# ESP32_WROVER_iot_module.net
KiCad netlist of a schematic drawn in EAGLE
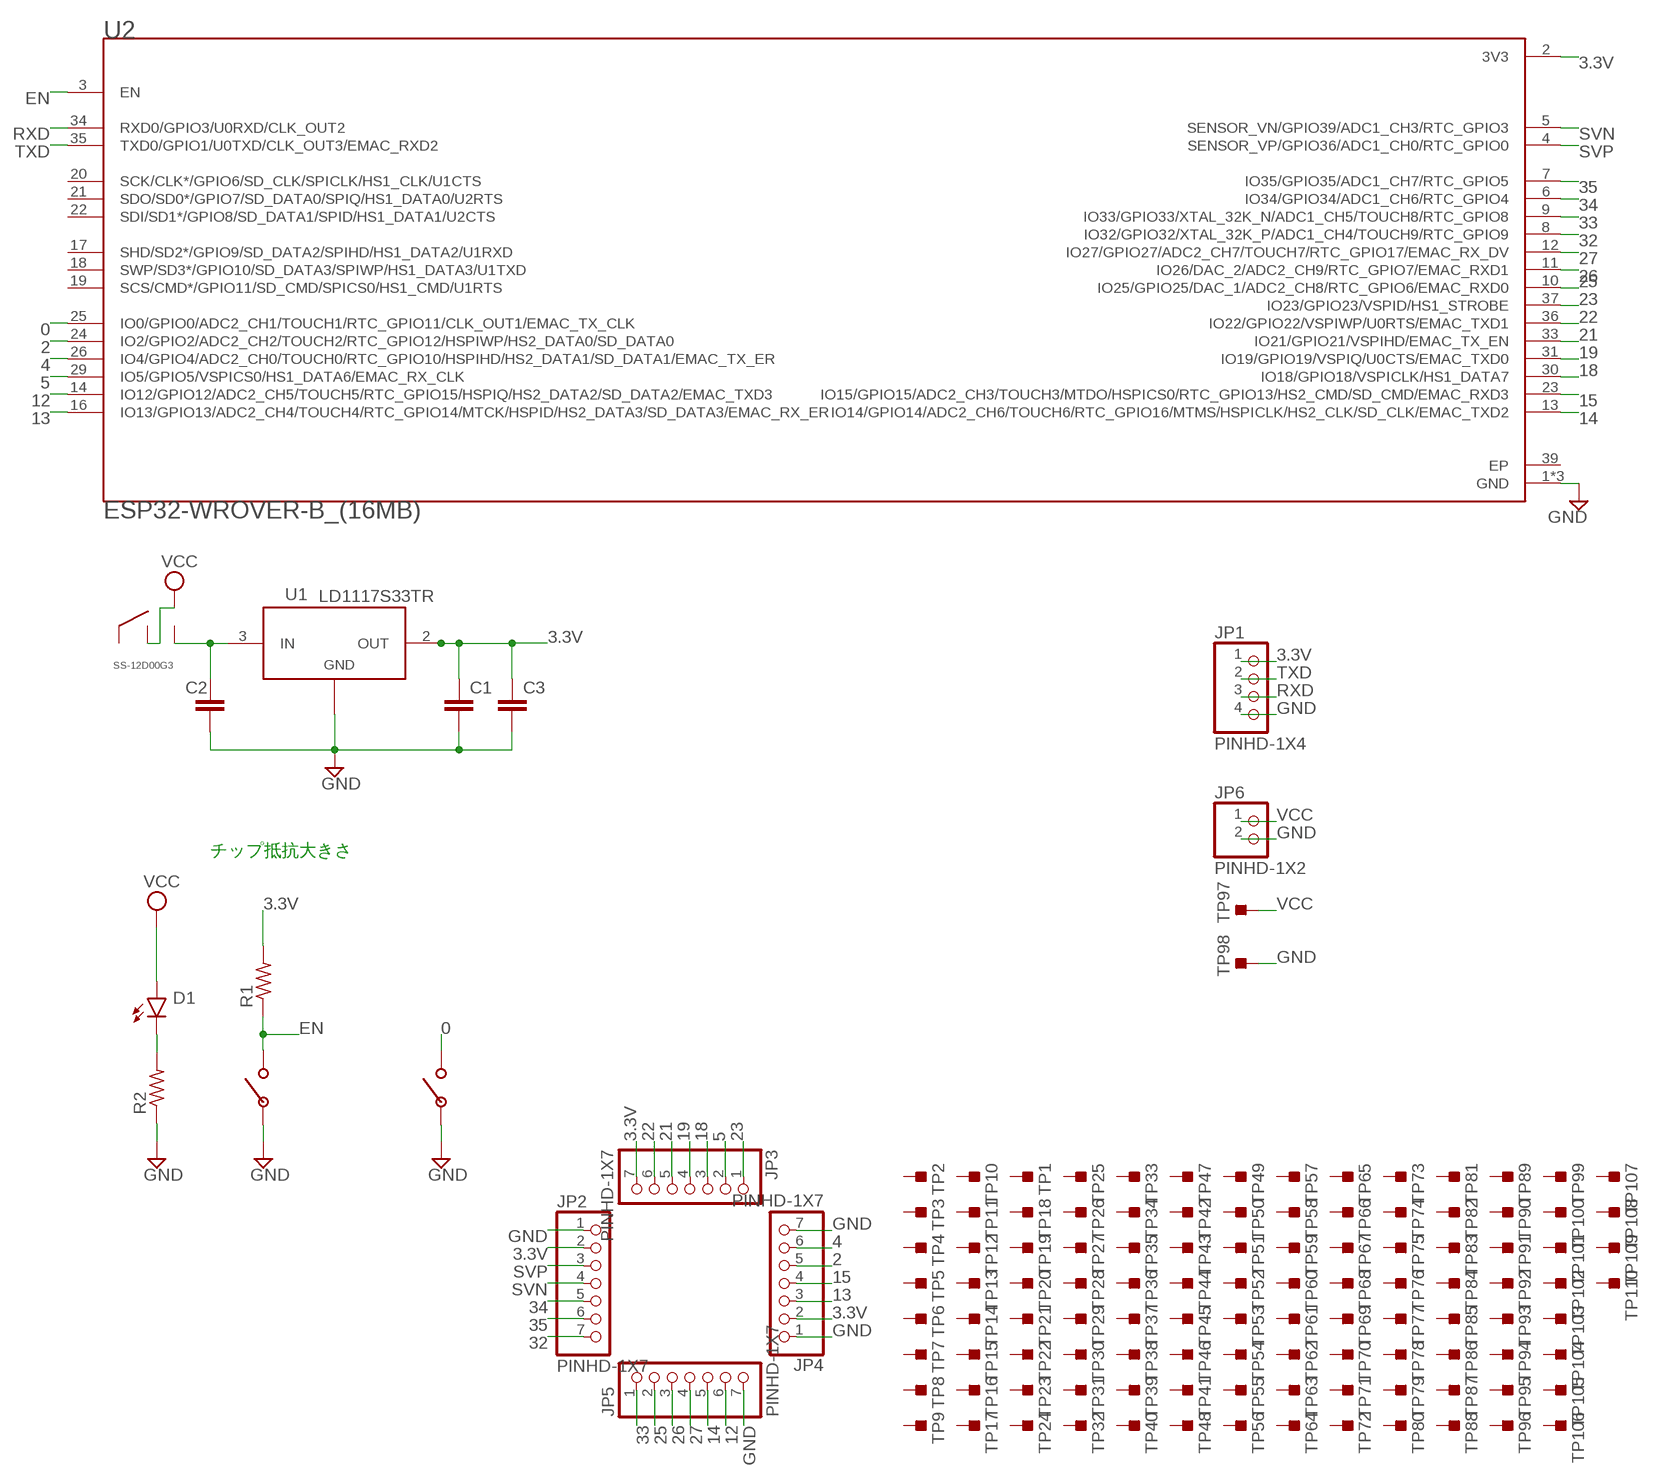
[diagram p0: schematic, sheet 1]

(export (version "E")
  (design (tool "Eeschema 10.0.6"))
  (components
    (comp (ref "C1")
      (value "C-EUC0805K")
      (footprint "eagle-import:C0805K")
      (libsource (lib "eagle-import") (part "C-EUC0805K"))
    )
    (comp (ref "C2")
      (value "C-EUC0805K")
      (footprint "eagle-import:C0805K")
      (libsource (lib "eagle-import") (part "C-EUC0805K"))
    )
    (comp (ref "C3")
      (value "C-EUC0805K")
      (footprint "eagle-import:C0805K")
      (libsource (lib "eagle-import") (part "C-EUC0805K"))
    )
    (comp (ref "D1")
      (value "LED_BLUE")
      (footprint "eagle-import:LEDC1608X39N_B")
      (libsource (lib "eagle-import") (part "LED_CHIPBLUE-1608_"))
    )
    (comp (ref "JP1")
      (value "PINHD-1X4")
      (footprint "eagle-import:1X04")
      (libsource (lib "eagle-import") (part "PINHD-1X4"))
    )
    (comp (ref "JP2")
      (value "PINHD-1X7")
      (footprint "eagle-import:1X07")
      (libsource (lib "eagle-import") (part "PINHD-1X7"))
    )
    (comp (ref "JP3")
      (value "PINHD-1X7")
      (footprint "eagle-import:1X07")
      (libsource (lib "eagle-import") (part "PINHD-1X7"))
    )
    (comp (ref "JP4")
      (value "PINHD-1X7")
      (footprint "eagle-import:1X07")
      (libsource (lib "eagle-import") (part "PINHD-1X7"))
    )
    (comp (ref "JP5")
      (value "PINHD-1X7")
      (footprint "eagle-import:1X07")
      (libsource (lib "eagle-import") (part "PINHD-1X7"))
    )
    (comp (ref "JP6")
      (value "PINHD-1X2")
      (footprint "eagle-import:1X02")
      (libsource (lib "eagle-import") (part "PINHD-1X2"))
    )
    (comp (ref "R1")
      (value "R-US_R0603")
      (footprint "eagle-import:R0603")
      (libsource (lib "eagle-import") (part "R-US_R0603"))
    )
    (comp (ref "R2")
      (value "R-US_R0603")
      (footprint "eagle-import:R0603")
      (libsource (lib "eagle-import") (part "R-US_R0603"))
    )
    (comp (ref "SW1")
      (value "TVAF06-A020B-R")
      (footprint "eagle-import:TVAF06-A020B-R")
      (libsource (lib "eagle-import") (part "TVAF06-A020B-R"))
    )
    (comp (ref "SW2")
      (value "TVAF06-A020B-R")
      (footprint "eagle-import:TVAF06-A020B-R")
      (libsource (lib "eagle-import") (part "TVAF06-A020B-R"))
    )
    (comp (ref "SW3")
      (value "SS-12D00G3")
      (footprint "eagle-import:SS-12D00G3")
      (libsource (lib "eagle-import") (part "SS-12D00G3"))
    )
    (comp (ref "TP1")
      (value "TESTPOINT_TPS-PAD-036")
      (footprint "eagle-import:TESTPOINT_PAD-036")
      (libsource (lib "eagle-import") (part "TESTPOINT_TPS-PAD-036"))
    )
    (comp (ref "TP2")
      (value "TESTPOINT_TPS-PAD-036")
      (footprint "eagle-import:TESTPOINT_PAD-036")
      (libsource (lib "eagle-import") (part "TESTPOINT_TPS-PAD-036"))
    )
    (comp (ref "TP3")
      (value "TESTPOINT_TPS-PAD-036")
      (footprint "eagle-import:TESTPOINT_PAD-036")
      (libsource (lib "eagle-import") (part "TESTPOINT_TPS-PAD-036"))
    )
    (comp (ref "TP4")
      (value "TESTPOINT_TPS-PAD-036")
      (footprint "eagle-import:TESTPOINT_PAD-036")
      (libsource (lib "eagle-import") (part "TESTPOINT_TPS-PAD-036"))
    )
    (comp (ref "TP5")
      (value "TESTPOINT_TPS-PAD-036")
      (footprint "eagle-import:TESTPOINT_PAD-036")
      (libsource (lib "eagle-import") (part "TESTPOINT_TPS-PAD-036"))
    )
    (comp (ref "TP6")
      (value "TESTPOINT_TPS-PAD-036")
      (footprint "eagle-import:TESTPOINT_PAD-036")
      (libsource (lib "eagle-import") (part "TESTPOINT_TPS-PAD-036"))
    )
    (comp (ref "TP7")
      (value "TESTPOINT_TPS-PAD-036")
      (footprint "eagle-import:TESTPOINT_PAD-036")
      (libsource (lib "eagle-import") (part "TESTPOINT_TPS-PAD-036"))
    )
    (comp (ref "TP8")
      (value "TESTPOINT_TPS-PAD-036")
      (footprint "eagle-import:TESTPOINT_PAD-036")
      (libsource (lib "eagle-import") (part "TESTPOINT_TPS-PAD-036"))
    )
    (comp (ref "TP9")
      (value "TESTPOINT_TPS-PAD-036")
      (footprint "eagle-import:TESTPOINT_PAD-036")
      (libsource (lib "eagle-import") (part "TESTPOINT_TPS-PAD-036"))
    )
    (comp (ref "TP10")
      (value "TESTPOINT_TPS-PAD-036")
      (footprint "eagle-import:TESTPOINT_PAD-036")
      (libsource (lib "eagle-import") (part "TESTPOINT_TPS-PAD-036"))
    )
    (comp (ref "TP11")
      (value "TESTPOINT_TPS-PAD-036")
      (footprint "eagle-import:TESTPOINT_PAD-036")
      (libsource (lib "eagle-import") (part "TESTPOINT_TPS-PAD-036"))
    )
    (comp (ref "TP12")
      (value "TESTPOINT_TPS-PAD-036")
      (footprint "eagle-import:TESTPOINT_PAD-036")
      (libsource (lib "eagle-import") (part "TESTPOINT_TPS-PAD-036"))
    )
    (comp (ref "TP13")
      (value "TESTPOINT_TPS-PAD-036")
      (footprint "eagle-import:TESTPOINT_PAD-036")
      (libsource (lib "eagle-import") (part "TESTPOINT_TPS-PAD-036"))
    )
    (comp (ref "TP14")
      (value "TESTPOINT_TPS-PAD-036")
      (footprint "eagle-import:TESTPOINT_PAD-036")
      (libsource (lib "eagle-import") (part "TESTPOINT_TPS-PAD-036"))
    )
    (comp (ref "TP15")
      (value "TESTPOINT_TPS-PAD-036")
      (footprint "eagle-import:TESTPOINT_PAD-036")
      (libsource (lib "eagle-import") (part "TESTPOINT_TPS-PAD-036"))
    )
    (comp (ref "TP16")
      (value "TESTPOINT_TPS-PAD-036")
      (footprint "eagle-import:TESTPOINT_PAD-036")
      (libsource (lib "eagle-import") (part "TESTPOINT_TPS-PAD-036"))
    )
    (comp (ref "TP17")
      (value "TESTPOINT_TPS-PAD-036")
      (footprint "eagle-import:TESTPOINT_PAD-036")
      (libsource (lib "eagle-import") (part "TESTPOINT_TPS-PAD-036"))
    )
    (comp (ref "TP18")
      (value "TESTPOINT_TPS-PAD-036")
      (footprint "eagle-import:TESTPOINT_PAD-036")
      (libsource (lib "eagle-import") (part "TESTPOINT_TPS-PAD-036"))
    )
    (comp (ref "TP19")
      (value "TESTPOINT_TPS-PAD-036")
      (footprint "eagle-import:TESTPOINT_PAD-036")
      (libsource (lib "eagle-import") (part "TESTPOINT_TPS-PAD-036"))
    )
    (comp (ref "TP20")
      (value "TESTPOINT_TPS-PAD-036")
      (footprint "eagle-import:TESTPOINT_PAD-036")
      (libsource (lib "eagle-import") (part "TESTPOINT_TPS-PAD-036"))
    )
    (comp (ref "TP21")
      (value "TESTPOINT_TPS-PAD-036")
      (footprint "eagle-import:TESTPOINT_PAD-036")
      (libsource (lib "eagle-import") (part "TESTPOINT_TPS-PAD-036"))
    )
    (comp (ref "TP22")
      (value "TESTPOINT_TPS-PAD-036")
      (footprint "eagle-import:TESTPOINT_PAD-036")
      (libsource (lib "eagle-import") (part "TESTPOINT_TPS-PAD-036"))
    )
    (comp (ref "TP23")
      (value "TESTPOINT_TPS-PAD-036")
      (footprint "eagle-import:TESTPOINT_PAD-036")
      (libsource (lib "eagle-import") (part "TESTPOINT_TPS-PAD-036"))
    )
    (comp (ref "TP24")
      (value "TESTPOINT_TPS-PAD-036")
      (footprint "eagle-import:TESTPOINT_PAD-036")
      (libsource (lib "eagle-import") (part "TESTPOINT_TPS-PAD-036"))
    )
    (comp (ref "TP25")
      (value "TESTPOINT_TPS-PAD-036")
      (footprint "eagle-import:TESTPOINT_PAD-036")
      (libsource (lib "eagle-import") (part "TESTPOINT_TPS-PAD-036"))
    )
    (comp (ref "TP26")
      (value "TESTPOINT_TPS-PAD-036")
      (footprint "eagle-import:TESTPOINT_PAD-036")
      (libsource (lib "eagle-import") (part "TESTPOINT_TPS-PAD-036"))
    )
    (comp (ref "TP27")
      (value "TESTPOINT_TPS-PAD-036")
      (footprint "eagle-import:TESTPOINT_PAD-036")
      (libsource (lib "eagle-import") (part "TESTPOINT_TPS-PAD-036"))
    )
    (comp (ref "TP28")
      (value "TESTPOINT_TPS-PAD-036")
      (footprint "eagle-import:TESTPOINT_PAD-036")
      (libsource (lib "eagle-import") (part "TESTPOINT_TPS-PAD-036"))
    )
    (comp (ref "TP29")
      (value "TESTPOINT_TPS-PAD-036")
      (footprint "eagle-import:TESTPOINT_PAD-036")
      (libsource (lib "eagle-import") (part "TESTPOINT_TPS-PAD-036"))
    )
    (comp (ref "TP30")
      (value "TESTPOINT_TPS-PAD-036")
      (footprint "eagle-import:TESTPOINT_PAD-036")
      (libsource (lib "eagle-import") (part "TESTPOINT_TPS-PAD-036"))
    )
    (comp (ref "TP31")
      (value "TESTPOINT_TPS-PAD-036")
      (footprint "eagle-import:TESTPOINT_PAD-036")
      (libsource (lib "eagle-import") (part "TESTPOINT_TPS-PAD-036"))
    )
    (comp (ref "TP32")
      (value "TESTPOINT_TPS-PAD-036")
      (footprint "eagle-import:TESTPOINT_PAD-036")
      (libsource (lib "eagle-import") (part "TESTPOINT_TPS-PAD-036"))
    )
    (comp (ref "TP33")
      (value "TESTPOINT_TPS-PAD-036")
      (footprint "eagle-import:TESTPOINT_PAD-036")
      (libsource (lib "eagle-import") (part "TESTPOINT_TPS-PAD-036"))
    )
    (comp (ref "TP34")
      (value "TESTPOINT_TPS-PAD-036")
      (footprint "eagle-import:TESTPOINT_PAD-036")
      (libsource (lib "eagle-import") (part "TESTPOINT_TPS-PAD-036"))
    )
    (comp (ref "TP35")
      (value "TESTPOINT_TPS-PAD-036")
      (footprint "eagle-import:TESTPOINT_PAD-036")
      (libsource (lib "eagle-import") (part "TESTPOINT_TPS-PAD-036"))
    )
    (comp (ref "TP36")
      (value "TESTPOINT_TPS-PAD-036")
      (footprint "eagle-import:TESTPOINT_PAD-036")
      (libsource (lib "eagle-import") (part "TESTPOINT_TPS-PAD-036"))
    )
    (comp (ref "TP37")
      (value "TESTPOINT_TPS-PAD-036")
      (footprint "eagle-import:TESTPOINT_PAD-036")
      (libsource (lib "eagle-import") (part "TESTPOINT_TPS-PAD-036"))
    )
    (comp (ref "TP38")
      (value "TESTPOINT_TPS-PAD-036")
      (footprint "eagle-import:TESTPOINT_PAD-036")
      (libsource (lib "eagle-import") (part "TESTPOINT_TPS-PAD-036"))
    )
    (comp (ref "TP39")
      (value "TESTPOINT_TPS-PAD-036")
      (footprint "eagle-import:TESTPOINT_PAD-036")
      (libsource (lib "eagle-import") (part "TESTPOINT_TPS-PAD-036"))
    )
    (comp (ref "TP40")
      (value "TESTPOINT_TPS-PAD-036")
      (footprint "eagle-import:TESTPOINT_PAD-036")
      (libsource (lib "eagle-import") (part "TESTPOINT_TPS-PAD-036"))
    )
    (comp (ref "TP41")
      (value "TESTPOINT_TPS-PAD-036")
      (footprint "eagle-import:TESTPOINT_PAD-036")
      (libsource (lib "eagle-import") (part "TESTPOINT_TPS-PAD-036"))
    )
    (comp (ref "TP42")
      (value "TESTPOINT_TPS-PAD-036")
      (footprint "eagle-import:TESTPOINT_PAD-036")
      (libsource (lib "eagle-import") (part "TESTPOINT_TPS-PAD-036"))
    )
    (comp (ref "TP43")
      (value "TESTPOINT_TPS-PAD-036")
      (footprint "eagle-import:TESTPOINT_PAD-036")
      (libsource (lib "eagle-import") (part "TESTPOINT_TPS-PAD-036"))
    )
    (comp (ref "TP44")
      (value "TESTPOINT_TPS-PAD-036")
      (footprint "eagle-import:TESTPOINT_PAD-036")
      (libsource (lib "eagle-import") (part "TESTPOINT_TPS-PAD-036"))
    )
    (comp (ref "TP45")
      (value "TESTPOINT_TPS-PAD-036")
      (footprint "eagle-import:TESTPOINT_PAD-036")
      (libsource (lib "eagle-import") (part "TESTPOINT_TPS-PAD-036"))
    )
    (comp (ref "TP46")
      (value "TESTPOINT_TPS-PAD-036")
      (footprint "eagle-import:TESTPOINT_PAD-036")
      (libsource (lib "eagle-import") (part "TESTPOINT_TPS-PAD-036"))
    )
    (comp (ref "TP47")
      (value "TESTPOINT_TPS-PAD-036")
      (footprint "eagle-import:TESTPOINT_PAD-036")
      (libsource (lib "eagle-import") (part "TESTPOINT_TPS-PAD-036"))
    )
    (comp (ref "TP48")
      (value "TESTPOINT_TPS-PAD-036")
      (footprint "eagle-import:TESTPOINT_PAD-036")
      (libsource (lib "eagle-import") (part "TESTPOINT_TPS-PAD-036"))
    )
    (comp (ref "TP49")
      (value "TESTPOINT_TPS-PAD-036")
      (footprint "eagle-import:TESTPOINT_PAD-036")
      (libsource (lib "eagle-import") (part "TESTPOINT_TPS-PAD-036"))
    )
    (comp (ref "TP50")
      (value "TESTPOINT_TPS-PAD-036")
      (footprint "eagle-import:TESTPOINT_PAD-036")
      (libsource (lib "eagle-import") (part "TESTPOINT_TPS-PAD-036"))
    )
    (comp (ref "TP51")
      (value "TESTPOINT_TPS-PAD-036")
      (footprint "eagle-import:TESTPOINT_PAD-036")
      (libsource (lib "eagle-import") (part "TESTPOINT_TPS-PAD-036"))
    )
    (comp (ref "TP52")
      (value "TESTPOINT_TPS-PAD-036")
      (footprint "eagle-import:TESTPOINT_PAD-036")
      (libsource (lib "eagle-import") (part "TESTPOINT_TPS-PAD-036"))
    )
    (comp (ref "TP53")
      (value "TESTPOINT_TPS-PAD-036")
      (footprint "eagle-import:TESTPOINT_PAD-036")
      (libsource (lib "eagle-import") (part "TESTPOINT_TPS-PAD-036"))
    )
    (comp (ref "TP54")
      (value "TESTPOINT_TPS-PAD-036")
      (footprint "eagle-import:TESTPOINT_PAD-036")
      (libsource (lib "eagle-import") (part "TESTPOINT_TPS-PAD-036"))
    )
    (comp (ref "TP55")
      (value "TESTPOINT_TPS-PAD-036")
      (footprint "eagle-import:TESTPOINT_PAD-036")
      (libsource (lib "eagle-import") (part "TESTPOINT_TPS-PAD-036"))
    )
    (comp (ref "TP56")
      (value "TESTPOINT_TPS-PAD-036")
      (footprint "eagle-import:TESTPOINT_PAD-036")
      (libsource (lib "eagle-import") (part "TESTPOINT_TPS-PAD-036"))
    )
    (comp (ref "TP57")
      (value "TESTPOINT_TPS-PAD-036")
      (footprint "eagle-import:TESTPOINT_PAD-036")
      (libsource (lib "eagle-import") (part "TESTPOINT_TPS-PAD-036"))
    )
    (comp (ref "TP58")
      (value "TESTPOINT_TPS-PAD-036")
      (footprint "eagle-import:TESTPOINT_PAD-036")
      (libsource (lib "eagle-import") (part "TESTPOINT_TPS-PAD-036"))
    )
    (comp (ref "TP59")
      (value "TESTPOINT_TPS-PAD-036")
      (footprint "eagle-import:TESTPOINT_PAD-036")
      (libsource (lib "eagle-import") (part "TESTPOINT_TPS-PAD-036"))
    )
    (comp (ref "TP60")
      (value "TESTPOINT_TPS-PAD-036")
      (footprint "eagle-import:TESTPOINT_PAD-036")
      (libsource (lib "eagle-import") (part "TESTPOINT_TPS-PAD-036"))
    )
    (comp (ref "TP61")
      (value "TESTPOINT_TPS-PAD-036")
      (footprint "eagle-import:TESTPOINT_PAD-036")
      (libsource (lib "eagle-import") (part "TESTPOINT_TPS-PAD-036"))
    )
    (comp (ref "TP62")
      (value "TESTPOINT_TPS-PAD-036")
      (footprint "eagle-import:TESTPOINT_PAD-036")
      (libsource (lib "eagle-import") (part "TESTPOINT_TPS-PAD-036"))
    )
    (comp (ref "TP63")
      (value "TESTPOINT_TPS-PAD-036")
      (footprint "eagle-import:TESTPOINT_PAD-036")
      (libsource (lib "eagle-import") (part "TESTPOINT_TPS-PAD-036"))
    )
    (comp (ref "TP64")
      (value "TESTPOINT_TPS-PAD-036")
      (footprint "eagle-import:TESTPOINT_PAD-036")
      (libsource (lib "eagle-import") (part "TESTPOINT_TPS-PAD-036"))
    )
    (comp (ref "TP65")
      (value "TESTPOINT_TPS-PAD-036")
      (footprint "eagle-import:TESTPOINT_PAD-036")
      (libsource (lib "eagle-import") (part "TESTPOINT_TPS-PAD-036"))
    )
    (comp (ref "TP66")
      (value "TESTPOINT_TPS-PAD-036")
      (footprint "eagle-import:TESTPOINT_PAD-036")
      (libsource (lib "eagle-import") (part "TESTPOINT_TPS-PAD-036"))
    )
    (comp (ref "TP67")
      (value "TESTPOINT_TPS-PAD-036")
      (footprint "eagle-import:TESTPOINT_PAD-036")
      (libsource (lib "eagle-import") (part "TESTPOINT_TPS-PAD-036"))
    )
    (comp (ref "TP68")
      (value "TESTPOINT_TPS-PAD-036")
      (footprint "eagle-import:TESTPOINT_PAD-036")
      (libsource (lib "eagle-import") (part "TESTPOINT_TPS-PAD-036"))
    )
    (comp (ref "TP69")
      (value "TESTPOINT_TPS-PAD-036")
      (footprint "eagle-import:TESTPOINT_PAD-036")
      (libsource (lib "eagle-import") (part "TESTPOINT_TPS-PAD-036"))
    )
    (comp (ref "TP70")
      (value "TESTPOINT_TPS-PAD-036")
      (footprint "eagle-import:TESTPOINT_PAD-036")
      (libsource (lib "eagle-import") (part "TESTPOINT_TPS-PAD-036"))
    )
    (comp (ref "TP71")
      (value "TESTPOINT_TPS-PAD-036")
      (footprint "eagle-import:TESTPOINT_PAD-036")
      (libsource (lib "eagle-import") (part "TESTPOINT_TPS-PAD-036"))
    )
    (comp (ref "TP72")
      (value "TESTPOINT_TPS-PAD-036")
      (footprint "eagle-import:TESTPOINT_PAD-036")
      (libsource (lib "eagle-import") (part "TESTPOINT_TPS-PAD-036"))
    )
    (comp (ref "TP73")
      (value "TESTPOINT_TPS-PAD-036")
      (footprint "eagle-import:TESTPOINT_PAD-036")
      (libsource (lib "eagle-import") (part "TESTPOINT_TPS-PAD-036"))
    )
    (comp (ref "TP74")
      (value "TESTPOINT_TPS-PAD-036")
      (footprint "eagle-import:TESTPOINT_PAD-036")
      (libsource (lib "eagle-import") (part "TESTPOINT_TPS-PAD-036"))
    )
    (comp (ref "TP75")
      (value "TESTPOINT_TPS-PAD-036")
      (footprint "eagle-import:TESTPOINT_PAD-036")
      (libsource (lib "eagle-import") (part "TESTPOINT_TPS-PAD-036"))
    )
    (comp (ref "TP76")
      (value "TESTPOINT_TPS-PAD-036")
      (footprint "eagle-import:TESTPOINT_PAD-036")
      (libsource (lib "eagle-import") (part "TESTPOINT_TPS-PAD-036"))
    )
    (comp (ref "TP77")
      (value "TESTPOINT_TPS-PAD-036")
      (footprint "eagle-import:TESTPOINT_PAD-036")
      (libsource (lib "eagle-import") (part "TESTPOINT_TPS-PAD-036"))
    )
    (comp (ref "TP78")
      (value "TESTPOINT_TPS-PAD-036")
      (footprint "eagle-import:TESTPOINT_PAD-036")
      (libsource (lib "eagle-import") (part "TESTPOINT_TPS-PAD-036"))
    )
    (comp (ref "TP79")
      (value "TESTPOINT_TPS-PAD-036")
      (footprint "eagle-import:TESTPOINT_PAD-036")
      (libsource (lib "eagle-import") (part "TESTPOINT_TPS-PAD-036"))
    )
    (comp (ref "TP80")
      (value "TESTPOINT_TPS-PAD-036")
      (footprint "eagle-import:TESTPOINT_PAD-036")
      (libsource (lib "eagle-import") (part "TESTPOINT_TPS-PAD-036"))
    )
    (comp (ref "TP81")
      (value "TESTPOINT_TPS-PAD-036")
      (footprint "eagle-import:TESTPOINT_PAD-036")
      (libsource (lib "eagle-import") (part "TESTPOINT_TPS-PAD-036"))
    )
    (comp (ref "TP82")
      (value "TESTPOINT_TPS-PAD-036")
      (footprint "eagle-import:TESTPOINT_PAD-036")
      (libsource (lib "eagle-import") (part "TESTPOINT_TPS-PAD-036"))
    )
    (comp (ref "TP83")
      (value "TESTPOINT_TPS-PAD-036")
      (footprint "eagle-import:TESTPOINT_PAD-036")
      (libsource (lib "eagle-import") (part "TESTPOINT_TPS-PAD-036"))
    )
    (comp (ref "TP84")
      (value "TESTPOINT_TPS-PAD-036")
      (footprint "eagle-import:TESTPOINT_PAD-036")
      (libsource (lib "eagle-import") (part "TESTPOINT_TPS-PAD-036"))
    )
    (comp (ref "TP85")
      (value "TESTPOINT_TPS-PAD-036")
      (footprint "eagle-import:TESTPOINT_PAD-036")
      (libsource (lib "eagle-import") (part "TESTPOINT_TPS-PAD-036"))
    )
    (comp (ref "TP86")
      (value "TESTPOINT_TPS-PAD-036")
      (footprint "eagle-import:TESTPOINT_PAD-036")
      (libsource (lib "eagle-import") (part "TESTPOINT_TPS-PAD-036"))
    )
    (comp (ref "TP87")
      (value "TESTPOINT_TPS-PAD-036")
      (footprint "eagle-import:TESTPOINT_PAD-036")
      (libsource (lib "eagle-import") (part "TESTPOINT_TPS-PAD-036"))
    )
    (comp (ref "TP88")
      (value "TESTPOINT_TPS-PAD-036")
      (footprint "eagle-import:TESTPOINT_PAD-036")
      (libsource (lib "eagle-import") (part "TESTPOINT_TPS-PAD-036"))
    )
    (comp (ref "TP89")
      (value "TESTPOINT_TPS-PAD-036")
      (footprint "eagle-import:TESTPOINT_PAD-036")
      (libsource (lib "eagle-import") (part "TESTPOINT_TPS-PAD-036"))
    )
    (comp (ref "TP90")
      (value "TESTPOINT_TPS-PAD-036")
      (footprint "eagle-import:TESTPOINT_PAD-036")
      (libsource (lib "eagle-import") (part "TESTPOINT_TPS-PAD-036"))
    )
    (comp (ref "TP91")
      (value "TESTPOINT_TPS-PAD-036")
      (footprint "eagle-import:TESTPOINT_PAD-036")
      (libsource (lib "eagle-import") (part "TESTPOINT_TPS-PAD-036"))
    )
    (comp (ref "TP92")
      (value "TESTPOINT_TPS-PAD-036")
      (footprint "eagle-import:TESTPOINT_PAD-036")
      (libsource (lib "eagle-import") (part "TESTPOINT_TPS-PAD-036"))
    )
    (comp (ref "TP93")
      (value "TESTPOINT_TPS-PAD-036")
      (footprint "eagle-import:TESTPOINT_PAD-036")
      (libsource (lib "eagle-import") (part "TESTPOINT_TPS-PAD-036"))
    )
    (comp (ref "TP94")
      (value "TESTPOINT_TPS-PAD-036")
      (footprint "eagle-import:TESTPOINT_PAD-036")
      (libsource (lib "eagle-import") (part "TESTPOINT_TPS-PAD-036"))
    )
    (comp (ref "TP95")
      (value "TESTPOINT_TPS-PAD-036")
      (footprint "eagle-import:TESTPOINT_PAD-036")
      (libsource (lib "eagle-import") (part "TESTPOINT_TPS-PAD-036"))
    )
    (comp (ref "TP96")
      (value "TESTPOINT_TPS-PAD-036")
      (footprint "eagle-import:TESTPOINT_PAD-036")
      (libsource (lib "eagle-import") (part "TESTPOINT_TPS-PAD-036"))
    )
    (comp (ref "TP97")
      (value "TESTPOINT_TPS-PAD-036")
      (footprint "eagle-import:TESTPOINT_PAD-036")
      (libsource (lib "eagle-import") (part "TESTPOINT_TPS-PAD-036"))
    )
    (comp (ref "TP98")
      (value "TESTPOINT_TPS-PAD-036")
      (footprint "eagle-import:TESTPOINT_PAD-036")
      (libsource (lib "eagle-import") (part "TESTPOINT_TPS-PAD-036"))
    )
    (comp (ref "TP99")
      (value "TESTPOINT_TPS-PAD-036")
      (footprint "eagle-import:TESTPOINT_PAD-036")
      (libsource (lib "eagle-import") (part "TESTPOINT_TPS-PAD-036"))
    )
    (comp (ref "TP100")
      (value "TESTPOINT_TPS-PAD-036")
      (footprint "eagle-import:TESTPOINT_PAD-036")
      (libsource (lib "eagle-import") (part "TESTPOINT_TPS-PAD-036"))
    )
    (comp (ref "TP101")
      (value "TESTPOINT_TPS-PAD-036")
      (footprint "eagle-import:TESTPOINT_PAD-036")
      (libsource (lib "eagle-import") (part "TESTPOINT_TPS-PAD-036"))
    )
    (comp (ref "TP102")
      (value "TESTPOINT_TPS-PAD-036")
      (footprint "eagle-import:TESTPOINT_PAD-036")
      (libsource (lib "eagle-import") (part "TESTPOINT_TPS-PAD-036"))
    )
    (comp (ref "TP103")
      (value "TESTPOINT_TPS-PAD-036")
      (footprint "eagle-import:TESTPOINT_PAD-036")
      (libsource (lib "eagle-import") (part "TESTPOINT_TPS-PAD-036"))
    )
    (comp (ref "TP104")
      (value "TESTPOINT_TPS-PAD-036")
      (footprint "eagle-import:TESTPOINT_PAD-036")
      (libsource (lib "eagle-import") (part "TESTPOINT_TPS-PAD-036"))
    )
    (comp (ref "TP105")
      (value "TESTPOINT_TPS-PAD-036")
      (footprint "eagle-import:TESTPOINT_PAD-036")
      (libsource (lib "eagle-import") (part "TESTPOINT_TPS-PAD-036"))
    )
    (comp (ref "TP106")
      (value "TESTPOINT_TPS-PAD-036")
      (footprint "eagle-import:TESTPOINT_PAD-036")
      (libsource (lib "eagle-import") (part "TESTPOINT_TPS-PAD-036"))
    )
    (comp (ref "TP107")
      (value "TESTPOINT_TPS-PAD-036")
      (footprint "eagle-import:TESTPOINT_PAD-036")
      (libsource (lib "eagle-import") (part "TESTPOINT_TPS-PAD-036"))
    )
    (comp (ref "TP108")
      (value "TESTPOINT_TPS-PAD-036")
      (footprint "eagle-import:TESTPOINT_PAD-036")
      (libsource (lib "eagle-import") (part "TESTPOINT_TPS-PAD-036"))
    )
    (comp (ref "TP109")
      (value "TESTPOINT_TPS-PAD-036")
      (footprint "eagle-import:TESTPOINT_PAD-036")
      (libsource (lib "eagle-import") (part "TESTPOINT_TPS-PAD-036"))
    )
    (comp (ref "TP110")
      (value "TESTPOINT_TPS-PAD-036")
      (footprint "eagle-import:TESTPOINT_PAD-036")
      (libsource (lib "eagle-import") (part "TESTPOINT_TPS-PAD-036"))
    )
    (comp (ref "U1")
      (value "LD1117S33TR")
      (footprint "eagle-import:SOT-223")
      (fields
        (field (name "DIGIKEY_PART_NUMBER") "497-1242-2-ND")
        (field (name "MANUFACTURER") "STMicroelectronics")
        (field (name "CREATED_BY") "PCBLayout.com")
      )
      (libsource (lib "eagle-import") (part "LD1117S33TR"))
    )
    (comp (ref "U2")
      (value "ESP32-WROVER-B_(16MB)")
      (footprint "eagle-import:XCVR_ESP32-WROVER-B_(16MB)")
      (fields (field (name "MF") "Espressif Systems") (field (name "MP") "ESP32-WROVER-B (16MB)"))
      (libsource (lib "eagle-import") (part "ESP32-WROVER-B_(16MB)"))
    )
  )
  (nets
    (net (code "1") (name "/0") (class "Default")
      (node (ref "SW2") (pin "P$1") (pinfunction "P$1_P$1") (pintype "bidirectional"))
      (node (ref "U2") (pin "25") (pinfunction "IO0/GPIO0/ADC2_CH1/TOUCH1/RTC_GPIO11/CLK_OUT1/EMAC_TX_CLK_25") (pintype "bidirectional"))
    )
    (net (code "2") (name "/2") (class "Default")
      (node (ref "JP4") (pin "5") (pinfunction "5_5") (pintype "passive"))
      (node (ref "U2") (pin "24") (pinfunction "IO2/GPIO2/ADC2_CH2/TOUCH2/RTC_GPIO12/HSPIWP/HS2_DATA0/SD_DATA0_24") (pintype "bidirectional"))
    )
    (net (code "3") (name "/3.3V") (class "Default")
      (node (ref "C1") (pin "1") (pinfunction "1_1") (pintype "passive"))
      (node (ref "C3") (pin "1") (pinfunction "1_1") (pintype "passive"))
      (node (ref "JP1") (pin "1") (pinfunction "1_1") (pintype "passive"))
      (node (ref "JP2") (pin "2") (pinfunction "2_2") (pintype "passive"))
      (node (ref "JP3") (pin "7") (pinfunction "7_7") (pintype "passive"))
      (node (ref "JP4") (pin "2") (pinfunction "2_2") (pintype "passive"))
      (node (ref "R1") (pin "2") (pinfunction "2_2") (pintype "passive"))
      (node (ref "U1") (pin "2") (pinfunction "OUT_2") (pintype "output"))
      (node (ref "U1") (pin "4") (pinfunction "4_4") (pintype "passive"))
      (node (ref "U2") (pin "2") (pinfunction "3V3_2") (pintype "power_in"))
    )
    (net (code "4") (name "/4") (class "Default")
      (node (ref "JP4") (pin "6") (pinfunction "6_6") (pintype "passive"))
      (node (ref "U2") (pin "26") (pinfunction "IO4/GPIO4/ADC2_CH0/TOUCH0/RTC_GPIO10/HSPIHD/HS2_DATA1/SD_DATA1/EMAC_TX_ER_26") (pintype "bidirectional"))
    )
    (net (code "5") (name "/5") (class "Default")
      (node (ref "JP3") (pin "2") (pinfunction "2_2") (pintype "passive"))
      (node (ref "U2") (pin "29") (pinfunction "IO5/GPIO5/VSPICS0/HS1_DATA6/EMAC_RX_CLK_29") (pintype "bidirectional"))
    )
    (net (code "6") (name "/12") (class "Default")
      (node (ref "JP5") (pin "6") (pinfunction "6_6") (pintype "passive"))
      (node (ref "U2") (pin "14") (pinfunction "IO12/GPIO12/ADC2_CH5/TOUCH5/RTC_GPIO15/HSPIQ/HS2_DATA2/SD_DATA2/EMAC_TXD3_14") (pintype "bidirectional"))
    )
    (net (code "7") (name "/13") (class "Default")
      (node (ref "JP4") (pin "3") (pinfunction "3_3") (pintype "passive"))
      (node (ref "U2") (pin "16") (pinfunction "IO13/GPIO13/ADC2_CH4/TOUCH4/RTC_GPIO14/MTCK/HSPID/HS2_DATA3/SD_DATA3/EMAC_RX_ER_16") (pintype "bidirectional"))
    )
    (net (code "8") (name "/14") (class "Default")
      (node (ref "JP5") (pin "5") (pinfunction "5_5") (pintype "passive"))
      (node (ref "U2") (pin "13") (pinfunction "IO14/GPIO14/ADC2_CH6/TOUCH6/RTC_GPIO16/MTMS/HSPICLK/HS2_CLK/SD_CLK/EMAC_TXD2_13") (pintype "bidirectional"))
    )
    (net (code "9") (name "/15") (class "Default")
      (node (ref "JP4") (pin "4") (pinfunction "4_4") (pintype "passive"))
      (node (ref "U2") (pin "23") (pinfunction "IO15/GPIO15/ADC2_CH3/TOUCH3/MTDO/HSPICS0/RTC_GPIO13/HS2_CMD/SD_CMD/EMAC_RXD3_23") (pintype "bidirectional"))
    )
    (net (code "10") (name "/18") (class "Default")
      (node (ref "JP3") (pin "3") (pinfunction "3_3") (pintype "passive"))
      (node (ref "U2") (pin "30") (pinfunction "IO18/GPIO18/VSPICLK/HS1_DATA7_30") (pintype "bidirectional"))
    )
    (net (code "11") (name "/19") (class "Default")
      (node (ref "JP3") (pin "4") (pinfunction "4_4") (pintype "passive"))
      (node (ref "U2") (pin "31") (pinfunction "IO19/GPIO19/VSPIQ/U0CTS/EMAC_TXD0_31") (pintype "bidirectional"))
    )
    (net (code "12") (name "/21") (class "Default")
      (node (ref "JP3") (pin "5") (pinfunction "5_5") (pintype "passive"))
      (node (ref "U2") (pin "33") (pinfunction "IO21/GPIO21/VSPIHD/EMAC_TX_EN_33") (pintype "bidirectional"))
    )
    (net (code "13") (name "/22") (class "Default")
      (node (ref "JP3") (pin "6") (pinfunction "6_6") (pintype "passive"))
      (node (ref "U2") (pin "36") (pinfunction "IO22/GPIO22/VSPIWP/U0RTS/EMAC_TXD1_36") (pintype "bidirectional"))
    )
    (net (code "14") (name "/23") (class "Default")
      (node (ref "JP3") (pin "1") (pinfunction "1_1") (pintype "passive"))
      (node (ref "U2") (pin "37") (pinfunction "IO23/GPIO23/VSPID/HS1_STROBE_37") (pintype "bidirectional"))
    )
    (net (code "15") (name "/25") (class "Default")
      (node (ref "JP5") (pin "2") (pinfunction "2_2") (pintype "passive"))
      (node (ref "U2") (pin "10") (pinfunction "IO25/GPIO25/DAC_1/ADC2_CH8/RTC_GPIO6/EMAC_RXD0_10") (pintype "bidirectional"))
    )
    (net (code "16") (name "/26") (class "Default")
      (node (ref "JP5") (pin "3") (pinfunction "3_3") (pintype "passive"))
      (node (ref "U2") (pin "11") (pinfunction "IO26/DAC_2/ADC2_CH9/RTC_GPIO7/EMAC_RXD1_11") (pintype "bidirectional"))
    )
    (net (code "17") (name "/27") (class "Default")
      (node (ref "JP5") (pin "4") (pinfunction "4_4") (pintype "passive"))
      (node (ref "U2") (pin "12") (pinfunction "IO27/GPIO27/ADC2_CH7/TOUCH7/RTC_GPIO17/EMAC_RX_DV_12") (pintype "bidirectional"))
    )
    (net (code "18") (name "/32") (class "Default")
      (node (ref "JP2") (pin "7") (pinfunction "7_7") (pintype "passive"))
      (node (ref "U2") (pin "8") (pinfunction "IO32/GPIO32/XTAL_32K_P/ADC1_CH4/TOUCH9/RTC_GPIO9_8") (pintype "bidirectional"))
    )
    (net (code "19") (name "/33") (class "Default")
      (node (ref "JP5") (pin "1") (pinfunction "1_1") (pintype "passive"))
      (node (ref "U2") (pin "9") (pinfunction "IO33/GPIO33/XTAL_32K_N/ADC1_CH5/TOUCH8/RTC_GPIO8_9") (pintype "bidirectional"))
    )
    (net (code "20") (name "/34") (class "Default")
      (node (ref "JP2") (pin "5") (pinfunction "5_5") (pintype "passive"))
      (node (ref "U2") (pin "6") (pinfunction "IO34/GPIO34/ADC1_CH6/RTC_GPIO4_6") (pintype "bidirectional"))
    )
    (net (code "21") (name "/35") (class "Default")
      (node (ref "JP2") (pin "6") (pinfunction "6_6") (pintype "passive"))
      (node (ref "U2") (pin "7") (pinfunction "IO35/GPIO35/ADC1_CH7/RTC_GPIO5_7") (pintype "bidirectional"))
    )
    (net (code "22") (name "/EN") (class "Default")
      (node (ref "R1") (pin "1") (pinfunction "1_1") (pintype "passive"))
      (node (ref "SW1") (pin "P$1") (pinfunction "P$1_P$1") (pintype "bidirectional"))
      (node (ref "U2") (pin "3") (pinfunction "EN_3") (pintype "input"))
    )
    (net (code "23") (name "/EP") (class "Default")
      (node (ref "U2") (pin "39") (pinfunction "EP_39") (pintype "power_in"))
    )
    (net (code "24") (name "/RXD") (class "Default")
      (node (ref "JP1") (pin "3") (pinfunction "3_3") (pintype "passive"))
      (node (ref "U2") (pin "34") (pinfunction "RXD0/GPIO3/U0RXD/CLK_OUT2_34") (pintype "bidirectional"))
    )
    (net (code "25") (name "/SVN") (class "Default")
      (node (ref "JP2") (pin "4") (pinfunction "4_4") (pintype "passive"))
      (node (ref "U2") (pin "5") (pinfunction "SENSOR_VN/GPIO39/ADC1_CH3/RTC_GPIO3_5") (pintype "bidirectional"))
    )
    (net (code "26") (name "/SVP") (class "Default")
      (node (ref "JP2") (pin "3") (pinfunction "3_3") (pintype "passive"))
      (node (ref "U2") (pin "4") (pinfunction "SENSOR_VP/GPIO36/ADC1_CH0/RTC_GPIO0_4") (pintype "bidirectional"))
    )
    (net (code "27") (name "/TXD") (class "Default")
      (node (ref "JP1") (pin "2") (pinfunction "2_2") (pintype "passive"))
      (node (ref "U2") (pin "35") (pinfunction "TXD0/GPIO1/U0TXD/CLK_OUT3/EMAC_RXD2_35") (pintype "bidirectional"))
    )
    (net (code "28") (name "GND") (class "Default")
      (node (ref "C1") (pin "2") (pinfunction "2_2") (pintype "passive"))
      (node (ref "C2") (pin "2") (pinfunction "2_2") (pintype "passive"))
      (node (ref "C3") (pin "2") (pinfunction "2_2") (pintype "passive"))
      (node (ref "JP1") (pin "4") (pinfunction "4_4") (pintype "passive"))
      (node (ref "JP2") (pin "1") (pinfunction "1_1") (pintype "passive"))
      (node (ref "JP4") (pin "1") (pinfunction "1_1") (pintype "passive"))
      (node (ref "JP4") (pin "7") (pinfunction "7_7") (pintype "passive"))
      (node (ref "JP5") (pin "7") (pinfunction "7_7") (pintype "passive"))
      (node (ref "JP6") (pin "2") (pinfunction "2_2") (pintype "passive"))
      (node (ref "R2") (pin "1") (pinfunction "1_1") (pintype "passive"))
      (node (ref "SW1") (pin "P$2") (pinfunction "P$2_P$2") (pintype "bidirectional"))
      (node (ref "SW2") (pin "P$2") (pinfunction "P$2_P$2") (pintype "bidirectional"))
      (node (ref "TP98") (pin "1") (pinfunction "TP_1") (pintype "passive"))
      (node (ref "U1") (pin "1") (pinfunction "ADJ/GND_1") (pintype "power_in"))
      (node (ref "U2") (pin "1") (pinfunction "GND_1") (pintype "power_in"))
      (node (ref "U2") (pin "15") (pinfunction "GND_15") (pintype "power_in"))
      (node (ref "U2") (pin "38") (pinfunction "GND_38") (pintype "power_in"))
    )
    (net (code "29") (name "Net-(D1-C)") (class "Default")
      (node (ref "D1") (pin "1") (pinfunction "C_1") (pintype "passive"))
      (node (ref "R2") (pin "2") (pinfunction "2_2") (pintype "passive"))
    )
    (net (code "30") (name "Net-(U1-IN)") (class "Default")
      (node (ref "C2") (pin "1") (pinfunction "1_1") (pintype "passive"))
      (node (ref "SW3") (pin "P$3") (pinfunction "P$3_P$3") (pintype "bidirectional"))
      (node (ref "U1") (pin "3") (pinfunction "IN_3") (pintype "input"))
    )
    (net (code "31") (name "VCC") (class "Default")
      (node (ref "D1") (pin "2") (pinfunction "A_2") (pintype "passive"))
      (node (ref "JP6") (pin "1") (pinfunction "1_1") (pintype "passive"))
      (node (ref "SW3") (pin "P$2") (pinfunction "P$2_P$2") (pintype "bidirectional"))
      (node (ref "TP97") (pin "1") (pinfunction "TP_1") (pintype "passive"))
    )
    (net (code "32") (name "unconnected-(SW3-PadP$1)") (class "Default")
      (node (ref "SW3") (pin "P$1") (pinfunction "P$1_P$1") (pintype "bidirectional"))
    )
    (net (code "33") (name "unconnected-(TP1-TP-Pad1)") (class "Default")
      (node (ref "TP1") (pin "1") (pinfunction "TP_1") (pintype "passive"))
    )
    (net (code "34") (name "unconnected-(TP2-TP-Pad1)") (class "Default")
      (node (ref "TP2") (pin "1") (pinfunction "TP_1") (pintype "passive"))
    )
    (net (code "35") (name "unconnected-(TP3-TP-Pad1)") (class "Default")
      (node (ref "TP3") (pin "1") (pinfunction "TP_1") (pintype "passive"))
    )
    (net (code "36") (name "unconnected-(TP4-TP-Pad1)") (class "Default")
      (node (ref "TP4") (pin "1") (pinfunction "TP_1") (pintype "passive"))
    )
    (net (code "37") (name "unconnected-(TP5-TP-Pad1)") (class "Default")
      (node (ref "TP5") (pin "1") (pinfunction "TP_1") (pintype "passive"))
    )
    (net (code "38") (name "unconnected-(TP6-TP-Pad1)") (class "Default")
      (node (ref "TP6") (pin "1") (pinfunction "TP_1") (pintype "passive"))
    )
    (net (code "39") (name "unconnected-(TP7-TP-Pad1)") (class "Default")
      (node (ref "TP7") (pin "1") (pinfunction "TP_1") (pintype "passive"))
    )
    (net (code "40") (name "unconnected-(TP8-TP-Pad1)") (class "Default")
      (node (ref "TP8") (pin "1") (pinfunction "TP_1") (pintype "passive"))
    )
    (net (code "41") (name "unconnected-(TP9-TP-Pad1)") (class "Default")
      (node (ref "TP9") (pin "1") (pinfunction "TP_1") (pintype "passive"))
    )
    (net (code "42") (name "unconnected-(TP10-TP-Pad1)") (class "Default")
      (node (ref "TP10") (pin "1") (pinfunction "TP_1") (pintype "passive"))
    )
    (net (code "43") (name "unconnected-(TP11-TP-Pad1)") (class "Default")
      (node (ref "TP11") (pin "1") (pinfunction "TP_1") (pintype "passive"))
    )
    (net (code "44") (name "unconnected-(TP12-TP-Pad1)") (class "Default")
      (node (ref "TP12") (pin "1") (pinfunction "TP_1") (pintype "passive"))
    )
    (net (code "45") (name "unconnected-(TP13-TP-Pad1)") (class "Default")
      (node (ref "TP13") (pin "1") (pinfunction "TP_1") (pintype "passive"))
    )
    (net (code "46") (name "unconnected-(TP14-TP-Pad1)") (class "Default")
      (node (ref "TP14") (pin "1") (pinfunction "TP_1") (pintype "passive"))
    )
    (net (code "47") (name "unconnected-(TP15-TP-Pad1)") (class "Default")
      (node (ref "TP15") (pin "1") (pinfunction "TP_1") (pintype "passive"))
    )
    (net (code "48") (name "unconnected-(TP16-TP-Pad1)") (class "Default")
      (node (ref "TP16") (pin "1") (pinfunction "TP_1") (pintype "passive"))
    )
    (net (code "49") (name "unconnected-(TP17-TP-Pad1)") (class "Default")
      (node (ref "TP17") (pin "1") (pinfunction "TP_1") (pintype "passive"))
    )
    (net (code "50") (name "unconnected-(TP18-TP-Pad1)") (class "Default")
      (node (ref "TP18") (pin "1") (pinfunction "TP_1") (pintype "passive"))
    )
    (net (code "51") (name "unconnected-(TP19-TP-Pad1)") (class "Default")
      (node (ref "TP19") (pin "1") (pinfunction "TP_1") (pintype "passive"))
    )
    (net (code "52") (name "unconnected-(TP20-TP-Pad1)") (class "Default")
      (node (ref "TP20") (pin "1") (pinfunction "TP_1") (pintype "passive"))
    )
    (net (code "53") (name "unconnected-(TP21-TP-Pad1)") (class "Default")
      (node (ref "TP21") (pin "1") (pinfunction "TP_1") (pintype "passive"))
    )
    (net (code "54") (name "unconnected-(TP22-TP-Pad1)") (class "Default")
      (node (ref "TP22") (pin "1") (pinfunction "TP_1") (pintype "passive"))
    )
    (net (code "55") (name "unconnected-(TP23-TP-Pad1)") (class "Default")
      (node (ref "TP23") (pin "1") (pinfunction "TP_1") (pintype "passive"))
    )
    (net (code "56") (name "unconnected-(TP24-TP-Pad1)") (class "Default")
      (node (ref "TP24") (pin "1") (pinfunction "TP_1") (pintype "passive"))
    )
    (net (code "57") (name "unconnected-(TP25-TP-Pad1)") (class "Default")
      (node (ref "TP25") (pin "1") (pinfunction "TP_1") (pintype "passive"))
    )
    (net (code "58") (name "unconnected-(TP26-TP-Pad1)") (class "Default")
      (node (ref "TP26") (pin "1") (pinfunction "TP_1") (pintype "passive"))
    )
    (net (code "59") (name "unconnected-(TP27-TP-Pad1)") (class "Default")
      (node (ref "TP27") (pin "1") (pinfunction "TP_1") (pintype "passive"))
    )
    (net (code "60") (name "unconnected-(TP28-TP-Pad1)") (class "Default")
      (node (ref "TP28") (pin "1") (pinfunction "TP_1") (pintype "passive"))
    )
    (net (code "61") (name "unconnected-(TP29-TP-Pad1)") (class "Default")
      (node (ref "TP29") (pin "1") (pinfunction "TP_1") (pintype "passive"))
    )
    (net (code "62") (name "unconnected-(TP30-TP-Pad1)") (class "Default")
      (node (ref "TP30") (pin "1") (pinfunction "TP_1") (pintype "passive"))
    )
    (net (code "63") (name "unconnected-(TP31-TP-Pad1)") (class "Default")
      (node (ref "TP31") (pin "1") (pinfunction "TP_1") (pintype "passive"))
    )
    (net (code "64") (name "unconnected-(TP32-TP-Pad1)") (class "Default")
      (node (ref "TP32") (pin "1") (pinfunction "TP_1") (pintype "passive"))
    )
    (net (code "65") (name "unconnected-(TP33-TP-Pad1)") (class "Default")
      (node (ref "TP33") (pin "1") (pinfunction "TP_1") (pintype "passive"))
    )
    (net (code "66") (name "unconnected-(TP34-TP-Pad1)") (class "Default")
      (node (ref "TP34") (pin "1") (pinfunction "TP_1") (pintype "passive"))
    )
    (net (code "67") (name "unconnected-(TP35-TP-Pad1)") (class "Default")
      (node (ref "TP35") (pin "1") (pinfunction "TP_1") (pintype "passive"))
    )
    (net (code "68") (name "unconnected-(TP36-TP-Pad1)") (class "Default")
      (node (ref "TP36") (pin "1") (pinfunction "TP_1") (pintype "passive"))
    )
    (net (code "69") (name "unconnected-(TP37-TP-Pad1)") (class "Default")
      (node (ref "TP37") (pin "1") (pinfunction "TP_1") (pintype "passive"))
    )
    (net (code "70") (name "unconnected-(TP38-TP-Pad1)") (class "Default")
      (node (ref "TP38") (pin "1") (pinfunction "TP_1") (pintype "passive"))
    )
    (net (code "71") (name "unconnected-(TP39-TP-Pad1)") (class "Default")
      (node (ref "TP39") (pin "1") (pinfunction "TP_1") (pintype "passive"))
    )
    (net (code "72") (name "unconnected-(TP40-TP-Pad1)") (class "Default")
      (node (ref "TP40") (pin "1") (pinfunction "TP_1") (pintype "passive"))
    )
    (net (code "73") (name "unconnected-(TP41-TP-Pad1)") (class "Default")
      (node (ref "TP41") (pin "1") (pinfunction "TP_1") (pintype "passive"))
    )
    (net (code "74") (name "unconnected-(TP42-TP-Pad1)") (class "Default")
      (node (ref "TP42") (pin "1") (pinfunction "TP_1") (pintype "passive"))
    )
    (net (code "75") (name "unconnected-(TP43-TP-Pad1)") (class "Default")
      (node (ref "TP43") (pin "1") (pinfunction "TP_1") (pintype "passive"))
    )
    (net (code "76") (name "unconnected-(TP44-TP-Pad1)") (class "Default")
      (node (ref "TP44") (pin "1") (pinfunction "TP_1") (pintype "passive"))
    )
    (net (code "77") (name "unconnected-(TP45-TP-Pad1)") (class "Default")
      (node (ref "TP45") (pin "1") (pinfunction "TP_1") (pintype "passive"))
    )
    (net (code "78") (name "unconnected-(TP46-TP-Pad1)") (class "Default")
      (node (ref "TP46") (pin "1") (pinfunction "TP_1") (pintype "passive"))
    )
    (net (code "79") (name "unconnected-(TP47-TP-Pad1)") (class "Default")
      (node (ref "TP47") (pin "1") (pinfunction "TP_1") (pintype "passive"))
    )
    (net (code "80") (name "unconnected-(TP48-TP-Pad1)") (class "Default")
      (node (ref "TP48") (pin "1") (pinfunction "TP_1") (pintype "passive"))
    )
    (net (code "81") (name "unconnected-(TP49-TP-Pad1)") (class "Default")
      (node (ref "TP49") (pin "1") (pinfunction "TP_1") (pintype "passive"))
    )
    (net (code "82") (name "unconnected-(TP50-TP-Pad1)") (class "Default")
      (node (ref "TP50") (pin "1") (pinfunction "TP_1") (pintype "passive"))
    )
    (net (code "83") (name "unconnected-(TP51-TP-Pad1)") (class "Default")
      (node (ref "TP51") (pin "1") (pinfunction "TP_1") (pintype "passive"))
    )
    (net (code "84") (name "unconnected-(TP52-TP-Pad1)") (class "Default")
      (node (ref "TP52") (pin "1") (pinfunction "TP_1") (pintype "passive"))
    )
    (net (code "85") (name "unconnected-(TP53-TP-Pad1)") (class "Default")
      (node (ref "TP53") (pin "1") (pinfunction "TP_1") (pintype "passive"))
    )
    (net (code "86") (name "unconnected-(TP54-TP-Pad1)") (class "Default")
      (node (ref "TP54") (pin "1") (pinfunction "TP_1") (pintype "passive"))
    )
    (net (code "87") (name "unconnected-(TP55-TP-Pad1)") (class "Default")
      (node (ref "TP55") (pin "1") (pinfunction "TP_1") (pintype "passive"))
    )
    (net (code "88") (name "unconnected-(TP56-TP-Pad1)") (class "Default")
      (node (ref "TP56") (pin "1") (pinfunction "TP_1") (pintype "passive"))
    )
    (net (code "89") (name "unconnected-(TP57-TP-Pad1)") (class "Default")
      (node (ref "TP57") (pin "1") (pinfunction "TP_1") (pintype "passive"))
    )
    (net (code "90") (name "unconnected-(TP58-TP-Pad1)") (class "Default")
      (node (ref "TP58") (pin "1") (pinfunction "TP_1") (pintype "passive"))
    )
    (net (code "91") (name "unconnected-(TP59-TP-Pad1)") (class "Default")
      (node (ref "TP59") (pin "1") (pinfunction "TP_1") (pintype "passive"))
    )
    (net (code "92") (name "unconnected-(TP60-TP-Pad1)") (class "Default")
      (node (ref "TP60") (pin "1") (pinfunction "TP_1") (pintype "passive"))
    )
    (net (code "93") (name "unconnected-(TP61-TP-Pad1)") (class "Default")
      (node (ref "TP61") (pin "1") (pinfunction "TP_1") (pintype "passive"))
    )
    (net (code "94") (name "unconnected-(TP62-TP-Pad1)") (class "Default")
      (node (ref "TP62") (pin "1") (pinfunction "TP_1") (pintype "passive"))
    )
    (net (code "95") (name "unconnected-(TP63-TP-Pad1)") (class "Default")
      (node (ref "TP63") (pin "1") (pinfunction "TP_1") (pintype "passive"))
    )
    (net (code "96") (name "unconnected-(TP64-TP-Pad1)") (class "Default")
      (node (ref "TP64") (pin "1") (pinfunction "TP_1") (pintype "passive"))
    )
    (net (code "97") (name "unconnected-(TP65-TP-Pad1)") (class "Default")
      (node (ref "TP65") (pin "1") (pinfunction "TP_1") (pintype "passive"))
    )
    (net (code "98") (name "unconnected-(TP66-TP-Pad1)") (class "Default")
      (node (ref "TP66") (pin "1") (pinfunction "TP_1") (pintype "passive"))
    )
    (net (code "99") (name "unconnected-(TP67-TP-Pad1)") (class "Default")
      (node (ref "TP67") (pin "1") (pinfunction "TP_1") (pintype "passive"))
    )
    (net (code "100") (name "unconnected-(TP68-TP-Pad1)") (class "Default")
      (node (ref "TP68") (pin "1") (pinfunction "TP_1") (pintype "passive"))
    )
    (net (code "101") (name "unconnected-(TP69-TP-Pad1)") (class "Default")
      (node (ref "TP69") (pin "1") (pinfunction "TP_1") (pintype "passive"))
    )
    (net (code "102") (name "unconnected-(TP70-TP-Pad1)") (class "Default")
      (node (ref "TP70") (pin "1") (pinfunction "TP_1") (pintype "passive"))
    )
    (net (code "103") (name "unconnected-(TP71-TP-Pad1)") (class "Default")
      (node (ref "TP71") (pin "1") (pinfunction "TP_1") (pintype "passive"))
    )
    (net (code "104") (name "unconnected-(TP72-TP-Pad1)") (class "Default")
      (node (ref "TP72") (pin "1") (pinfunction "TP_1") (pintype "passive"))
    )
    (net (code "105") (name "unconnected-(TP73-TP-Pad1)") (class "Default")
      (node (ref "TP73") (pin "1") (pinfunction "TP_1") (pintype "passive"))
    )
    (net (code "106") (name "unconnected-(TP74-TP-Pad1)") (class "Default")
      (node (ref "TP74") (pin "1") (pinfunction "TP_1") (pintype "passive"))
    )
    (net (code "107") (name "unconnected-(TP75-TP-Pad1)") (class "Default")
      (node (ref "TP75") (pin "1") (pinfunction "TP_1") (pintype "passive"))
    )
    (net (code "108") (name "unconnected-(TP76-TP-Pad1)") (class "Default")
      (node (ref "TP76") (pin "1") (pinfunction "TP_1") (pintype "passive"))
    )
    (net (code "109") (name "unconnected-(TP77-TP-Pad1)") (class "Default")
      (node (ref "TP77") (pin "1") (pinfunction "TP_1") (pintype "passive"))
    )
    (net (code "110") (name "unconnected-(TP78-TP-Pad1)") (class "Default")
      (node (ref "TP78") (pin "1") (pinfunction "TP_1") (pintype "passive"))
    )
    (net (code "111") (name "unconnected-(TP79-TP-Pad1)") (class "Default")
      (node (ref "TP79") (pin "1") (pinfunction "TP_1") (pintype "passive"))
    )
    (net (code "112") (name "unconnected-(TP80-TP-Pad1)") (class "Default")
      (node (ref "TP80") (pin "1") (pinfunction "TP_1") (pintype "passive"))
    )
    (net (code "113") (name "unconnected-(TP81-TP-Pad1)") (class "Default")
      (node (ref "TP81") (pin "1") (pinfunction "TP_1") (pintype "passive"))
    )
    (net (code "114") (name "unconnected-(TP82-TP-Pad1)") (class "Default")
      (node (ref "TP82") (pin "1") (pinfunction "TP_1") (pintype "passive"))
    )
    (net (code "115") (name "unconnected-(TP83-TP-Pad1)") (class "Default")
      (node (ref "TP83") (pin "1") (pinfunction "TP_1") (pintype "passive"))
    )
    (net (code "116") (name "unconnected-(TP84-TP-Pad1)") (class "Default")
      (node (ref "TP84") (pin "1") (pinfunction "TP_1") (pintype "passive"))
    )
    (net (code "117") (name "unconnected-(TP85-TP-Pad1)") (class "Default")
      (node (ref "TP85") (pin "1") (pinfunction "TP_1") (pintype "passive"))
    )
    (net (code "118") (name "unconnected-(TP86-TP-Pad1)") (class "Default")
      (node (ref "TP86") (pin "1") (pinfunction "TP_1") (pintype "passive"))
    )
    (net (code "119") (name "unconnected-(TP87-TP-Pad1)") (class "Default")
      (node (ref "TP87") (pin "1") (pinfunction "TP_1") (pintype "passive"))
    )
    (net (code "120") (name "unconnected-(TP88-TP-Pad1)") (class "Default")
      (node (ref "TP88") (pin "1") (pinfunction "TP_1") (pintype "passive"))
    )
    (net (code "121") (name "unconnected-(TP89-TP-Pad1)") (class "Default")
      (node (ref "TP89") (pin "1") (pinfunction "TP_1") (pintype "passive"))
    )
    (net (code "122") (name "unconnected-(TP90-TP-Pad1)") (class "Default")
      (node (ref "TP90") (pin "1") (pinfunction "TP_1") (pintype "passive"))
    )
    (net (code "123") (name "unconnected-(TP91-TP-Pad1)") (class "Default")
      (node (ref "TP91") (pin "1") (pinfunction "TP_1") (pintype "passive"))
    )
    (net (code "124") (name "unconnected-(TP92-TP-Pad1)") (class "Default")
      (node (ref "TP92") (pin "1") (pinfunction "TP_1") (pintype "passive"))
    )
    (net (code "125") (name "unconnected-(TP93-TP-Pad1)") (class "Default")
      (node (ref "TP93") (pin "1") (pinfunction "TP_1") (pintype "passive"))
    )
    (net (code "126") (name "unconnected-(TP94-TP-Pad1)") (class "Default")
      (node (ref "TP94") (pin "1") (pinfunction "TP_1") (pintype "passive"))
    )
    (net (code "127") (name "unconnected-(TP95-TP-Pad1)") (class "Default")
      (node (ref "TP95") (pin "1") (pinfunction "TP_1") (pintype "passive"))
    )
    (net (code "128") (name "unconnected-(TP96-TP-Pad1)") (class "Default")
      (node (ref "TP96") (pin "1") (pinfunction "TP_1") (pintype "passive"))
    )
    (net (code "129") (name "unconnected-(TP99-TP-Pad1)") (class "Default")
      (node (ref "TP99") (pin "1") (pinfunction "TP_1") (pintype "passive"))
    )
    (net (code "130") (name "unconnected-(TP100-TP-Pad1)") (class "Default")
      (node (ref "TP100") (pin "1") (pinfunction "TP_1") (pintype "passive"))
    )
    (net (code "131") (name "unconnected-(TP101-TP-Pad1)") (class "Default")
      (node (ref "TP101") (pin "1") (pinfunction "TP_1") (pintype "passive"))
    )
    (net (code "132") (name "unconnected-(TP102-TP-Pad1)") (class "Default")
      (node (ref "TP102") (pin "1") (pinfunction "TP_1") (pintype "passive"))
    )
    (net (code "133") (name "unconnected-(TP103-TP-Pad1)") (class "Default")
      (node (ref "TP103") (pin "1") (pinfunction "TP_1") (pintype "passive"))
    )
    (net (code "134") (name "unconnected-(TP104-TP-Pad1)") (class "Default")
      (node (ref "TP104") (pin "1") (pinfunction "TP_1") (pintype "passive"))
    )
    (net (code "135") (name "unconnected-(TP105-TP-Pad1)") (class "Default")
      (node (ref "TP105") (pin "1") (pinfunction "TP_1") (pintype "passive"))
    )
    (net (code "136") (name "unconnected-(TP106-TP-Pad1)") (class "Default")
      (node (ref "TP106") (pin "1") (pinfunction "TP_1") (pintype "passive"))
    )
    (net (code "137") (name "unconnected-(TP107-TP-Pad1)") (class "Default")
      (node (ref "TP107") (pin "1") (pinfunction "TP_1") (pintype "passive"))
    )
    (net (code "138") (name "unconnected-(TP108-TP-Pad1)") (class "Default")
      (node (ref "TP108") (pin "1") (pinfunction "TP_1") (pintype "passive"))
    )
    (net (code "139") (name "unconnected-(TP109-TP-Pad1)") (class "Default")
      (node (ref "TP109") (pin "1") (pinfunction "TP_1") (pintype "passive"))
    )
    (net (code "140") (name "unconnected-(TP110-TP-Pad1)") (class "Default")
      (node (ref "TP110") (pin "1") (pinfunction "TP_1") (pintype "passive"))
    )
    (net (code "141") (name "unconnected-(U2-SCK{slash}CLK*{slash}GPIO6{slash}SD_CLK{slash}SPICLK{slash}HS1_CLK{slash}U1CTS-Pad20)") (class "Default")
      (node (ref "U2") (pin "20") (pinfunction "SCK/CLK*/GPIO6/SD_CLK/SPICLK/HS1_CLK/U1CTS_20") (pintype "bidirectional"))
    )
    (net (code "142") (name "unconnected-(U2-SCS{slash}CMD*{slash}GPIO11{slash}SD_CMD{slash}SPICS0{slash}HS1_CMD{slash}U1RTS-Pad19)") (class "Default")
      (node (ref "U2") (pin "19") (pinfunction "SCS/CMD*/GPIO11/SD_CMD/SPICS0/HS1_CMD/U1RTS_19") (pintype "bidirectional"))
    )
    (net (code "143") (name "unconnected-(U2-SDI{slash}SD1*{slash}GPIO8{slash}SD_DATA1{slash}SPID{slash}HS1_DATA1{slash}U2CTS-Pad22)") (class "Default")
      (node (ref "U2") (pin "22") (pinfunction "SDI/SD1*/GPIO8/SD_DATA1/SPID/HS1_DATA1/U2CTS_22") (pintype "bidirectional"))
    )
    (net (code "144") (name "unconnected-(U2-SDO{slash}SD0*{slash}GPIO7{slash}SD_DATA0{slash}SPIQ{slash}HS1_DATA0{slash}U2RTS-Pad21)") (class "Default")
      (node (ref "U2") (pin "21") (pinfunction "SDO/SD0*/GPIO7/SD_DATA0/SPIQ/HS1_DATA0/U2RTS_21") (pintype "bidirectional"))
    )
    (net (code "145") (name "unconnected-(U2-SHD{slash}SD2*{slash}GPIO9{slash}SD_DATA2{slash}SPIHD{slash}HS1_DATA2{slash}U1RXD-Pad17)") (class "Default")
      (node (ref "U2") (pin "17") (pinfunction "SHD/SD2*/GPIO9/SD_DATA2/SPIHD/HS1_DATA2/U1RXD_17") (pintype "bidirectional"))
    )
    (net (code "146") (name "unconnected-(U2-SWP{slash}SD3*{slash}GPIO10{slash}SD_DATA3{slash}SPIWP{slash}HS1_DATA3{slash}U1TXD-Pad18)") (class "Default")
      (node (ref "U2") (pin "18") (pinfunction "SWP/SD3*/GPIO10/SD_DATA3/SPIWP/HS1_DATA3/U1TXD_18") (pintype "bidirectional"))
    )
  )
)
